# Current_Sensor.net
KiCad netlist of a schematic drawn in Altium Designer
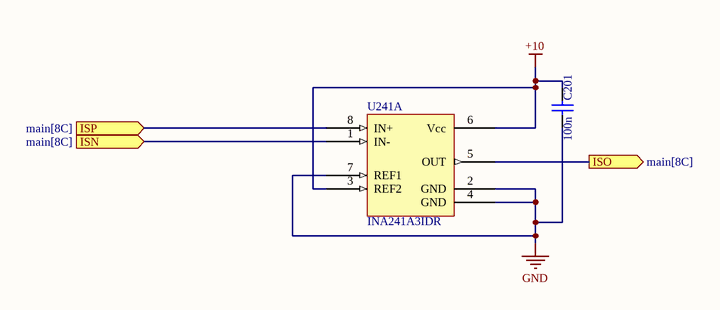
[diagram p0: Current_Sensor.SchDoc]

(export (version "E")
  (design (tool "Eeschema 10.0.6"))
  (components
    (comp (ref "C201")
      (value "100n")
      (footprint "CAP_1206")
      (description "Non Polarized Capacitor, SMD, 1206")
      (libsource (lib "Resistors and Capacitors") (part "CAPN 1206"))
    )
    (comp (ref "U241A")
      (value "INA241A3IDR")
      (footprint "SOIC8_M")
      (description "Current Sense Amp")
      (libsource (lib "Projects_2025") (part "INA241A3IDR"))
    )
  )
  (nets
    (net (code "1") (name "+10") (class "Default")
      (node (ref "C201") (pin "2") (pinfunction "2_2") (pintype "passive"))
      (node (ref "U241A") (pin "3") (pinfunction "REF2_3") (pintype "input"))
      (node (ref "U241A") (pin "6") (pinfunction "Vcc_6") (pintype "power_in"))
    )
    (net (code "2") (name "/ISN") (class "Default")
      (node (ref "U241A") (pin "1") (pinfunction "IN-_1") (pintype "input"))
    )
    (net (code "3") (name "/ISO") (class "Default")
      (node (ref "U241A") (pin "5") (pinfunction "OUT_5") (pintype "output"))
    )
    (net (code "4") (name "/ISP") (class "Default")
      (node (ref "U241A") (pin "8") (pinfunction "IN+_8") (pintype "input"))
    )
    (net (code "5") (name "GND") (class "Default")
      (node (ref "C201") (pin "1") (pinfunction "1_1") (pintype "passive"))
      (node (ref "U241A") (pin "2") (pinfunction "GND_2") (pintype "power_in"))
      (node (ref "U241A") (pin "4") (pinfunction "GND_4") (pintype "passive"))
      (node (ref "U241A") (pin "7") (pinfunction "REF1_7") (pintype "input"))
    )
  )
)
